# Controller.net
KiCad netlist of a schematic drawn in EAGLE
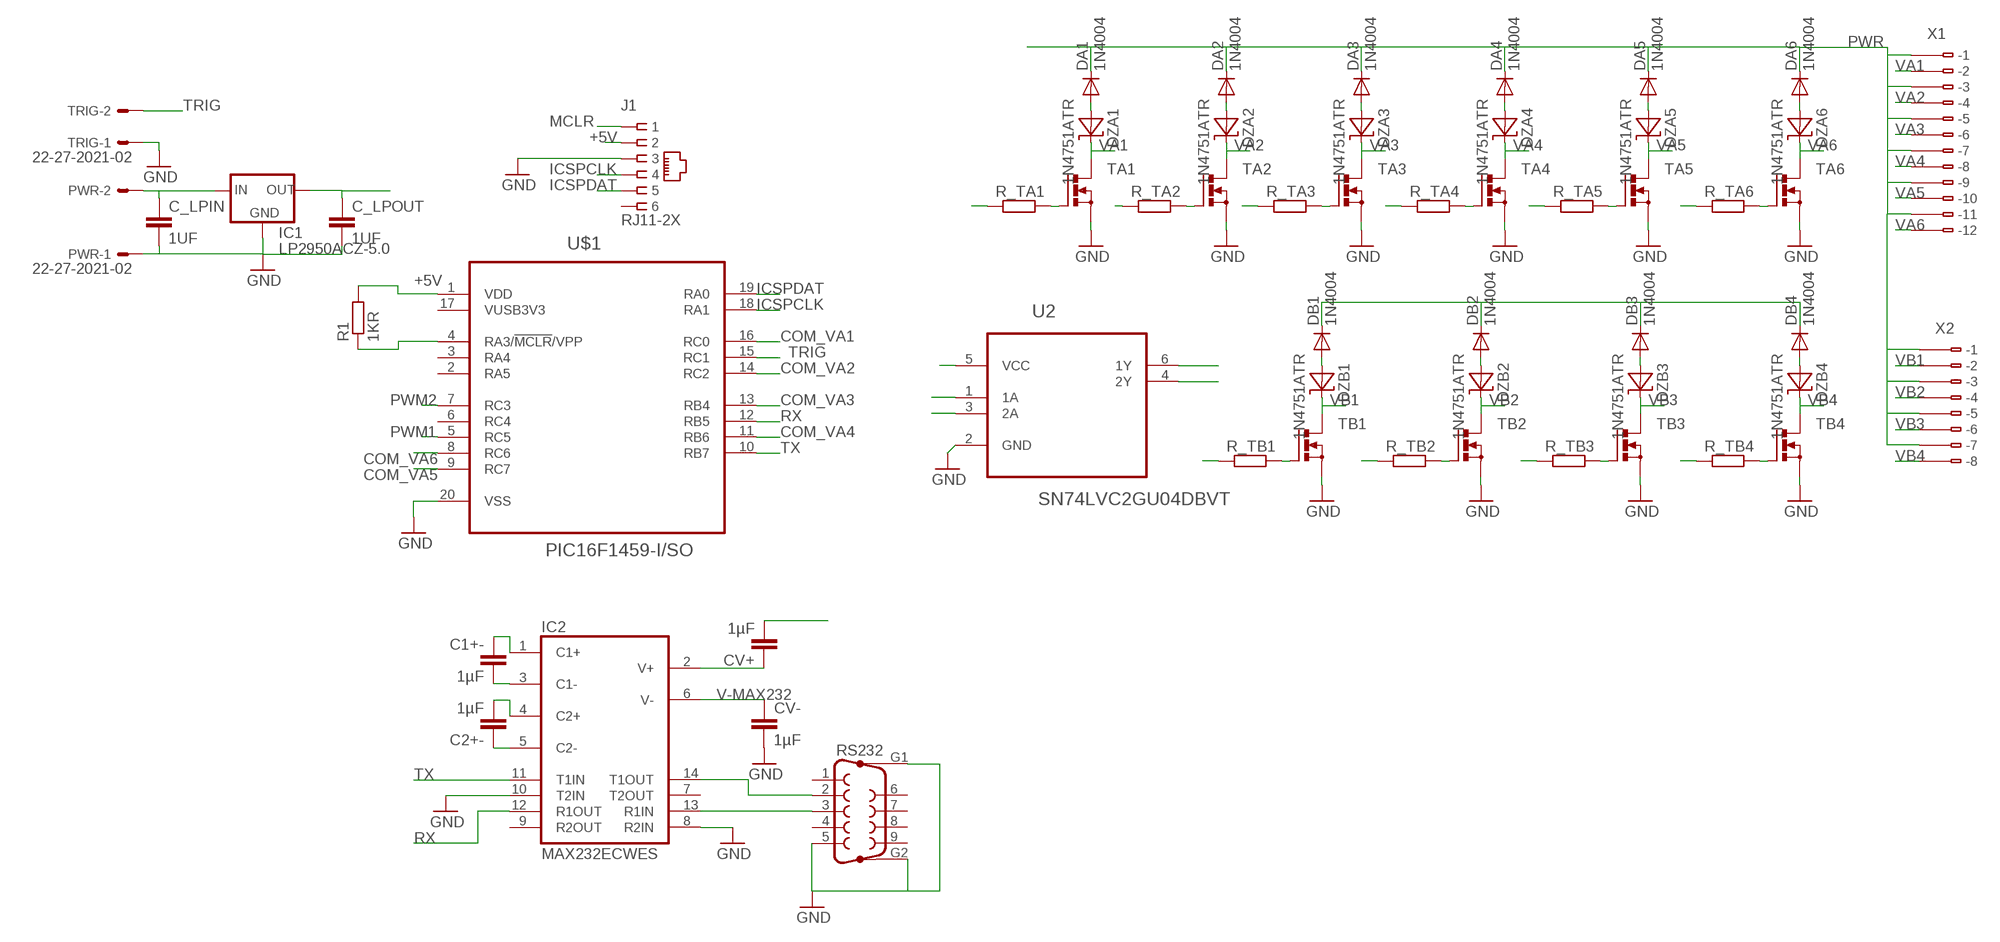
[diagram p0: schematic, sheet 1]

(export (version "E")
  (design (tool "Eeschema 10.0.6"))
  (components
    (comp (ref "C1+-")
      (value "1µF")
      (footprint "eagle-import:C0805")
      (libsource (lib "eagle-import") (part "C-EUC0805"))
    )
    (comp (ref "C2+-")
      (value "1µF")
      (footprint "eagle-import:C0805")
      (libsource (lib "eagle-import") (part "C-EUC0805"))
    )
    (comp (ref "CV+")
      (value "1µF")
      (footprint "eagle-import:C0805")
      (libsource (lib "eagle-import") (part "C-EUC0805"))
    )
    (comp (ref "CV-")
      (value "1µF")
      (footprint "eagle-import:C0805")
      (libsource (lib "eagle-import") (part "C-EUC0805"))
    )
    (comp (ref "C_LPIN")
      (value "1UF")
      (footprint "eagle-import:C0805")
      (libsource (lib "eagle-import") (part "C-EUC0805"))
    )
    (comp (ref "C_LPOUT")
      (value "1UF")
      (footprint "eagle-import:C0805")
      (libsource (lib "eagle-import") (part "C-EUC0805"))
    )
    (comp (ref "DA1")
      (value "1N4004")
      (footprint "eagle-import:DO41-10")
      (libsource (lib "eagle-import") (part "1N4004"))
    )
    (comp (ref "DA2")
      (value "1N4004")
      (footprint "eagle-import:DO41-10")
      (libsource (lib "eagle-import") (part "1N4004"))
    )
    (comp (ref "DA3")
      (value "1N4004")
      (footprint "eagle-import:DO41-10")
      (libsource (lib "eagle-import") (part "1N4004"))
    )
    (comp (ref "DA4")
      (value "1N4004")
      (footprint "eagle-import:DO41-10")
      (libsource (lib "eagle-import") (part "1N4004"))
    )
    (comp (ref "DA5")
      (value "1N4004")
      (footprint "eagle-import:DO41-10")
      (libsource (lib "eagle-import") (part "1N4004"))
    )
    (comp (ref "DA6")
      (value "1N4004")
      (footprint "eagle-import:DO41-10")
      (libsource (lib "eagle-import") (part "1N4004"))
    )
    (comp (ref "DB1")
      (value "1N4004")
      (footprint "eagle-import:DO41-10")
      (libsource (lib "eagle-import") (part "1N4004"))
    )
    (comp (ref "DB2")
      (value "1N4004")
      (footprint "eagle-import:DO41-10")
      (libsource (lib "eagle-import") (part "1N4004"))
    )
    (comp (ref "DB3")
      (value "1N4004")
      (footprint "eagle-import:DO41-10")
      (libsource (lib "eagle-import") (part "1N4004"))
    )
    (comp (ref "DB4")
      (value "1N4004")
      (footprint "eagle-import:DO41-10")
      (libsource (lib "eagle-import") (part "1N4004"))
    )
    (comp (ref "DZA1")
      (value "1N4751ATR")
      (footprint "eagle-import:DO41-7")
      (libsource (lib "eagle-import") (part "1N4751ATR"))
    )
    (comp (ref "DZA2")
      (value "1N4751ATR")
      (footprint "eagle-import:DO41-7")
      (libsource (lib "eagle-import") (part "1N4751ATR"))
    )
    (comp (ref "DZA3")
      (value "1N4751ATR")
      (footprint "eagle-import:DO41-7")
      (libsource (lib "eagle-import") (part "1N4751ATR"))
    )
    (comp (ref "DZA4")
      (value "1N4751ATR")
      (footprint "eagle-import:DO41-7")
      (libsource (lib "eagle-import") (part "1N4751ATR"))
    )
    (comp (ref "DZA5")
      (value "1N4751ATR")
      (footprint "eagle-import:DO41-7")
      (libsource (lib "eagle-import") (part "1N4751ATR"))
    )
    (comp (ref "DZA6")
      (value "1N4751ATR")
      (footprint "eagle-import:DO41-7")
      (libsource (lib "eagle-import") (part "1N4751ATR"))
    )
    (comp (ref "DZB1")
      (value "1N4751ATR")
      (footprint "eagle-import:DO41-7")
      (libsource (lib "eagle-import") (part "1N4751ATR"))
    )
    (comp (ref "DZB2")
      (value "1N4751ATR")
      (footprint "eagle-import:DO41-7")
      (libsource (lib "eagle-import") (part "1N4751ATR"))
    )
    (comp (ref "DZB3")
      (value "1N4751ATR")
      (footprint "eagle-import:DO41-7")
      (libsource (lib "eagle-import") (part "1N4751ATR"))
    )
    (comp (ref "DZB4")
      (value "1N4751ATR")
      (footprint "eagle-import:DO41-7")
      (libsource (lib "eagle-import") (part "1N4751ATR"))
    )
    (comp (ref "IC1")
      (value "LP2950ACZ-5.0")
      (footprint "eagle-import:TO92")
      (libsource (lib "eagle-import") (part "LP2950?ACZ-5.0"))
    )
    (comp (ref "IC2")
      (value "MAX232ECWES")
      (footprint "eagle-import:SO16")
      (libsource (lib "eagle-import") (part "MAX232ECWES"))
    )
    (comp (ref "J1")
      (value "RJ11-2X")
      (footprint "eagle-import:RJ11-NO_SHIELD")
      (fields (field (name "OC_FARNELL") "3363132"))
      (libsource (lib "eagle-import") (part "RJ11-2X"))
    )
    (comp (ref "PWR")
      (value "22-27-2021-02")
      (footprint "eagle-import:6410-02")
      (fields (field (name "OC_FARNELL") "9731148+1654528+1462641"))
      (libsource (lib "eagle-import") (part "22-?-0227-2021"))
    )
    (comp (ref "R1")
      (value "1KR")
      (footprint "eagle-import:R0805")
      (libsource (lib "eagle-import") (part "R-EU_R0805"))
    )
    (comp (ref "RS232")
      (value "F09HP")
      (footprint "eagle-import:F09HP")
      (fields (field (name "OC_FARNELL") "1084701"))
      (libsource (lib "eagle-import") (part "F09HP"))
    )
    (comp (ref "R_TA1")
      (value "R-EU_R0805")
      (footprint "eagle-import:R0805")
      (libsource (lib "eagle-import") (part "R-EU_R0805"))
    )
    (comp (ref "R_TA2")
      (value "R-EU_R0805")
      (footprint "eagle-import:R0805")
      (libsource (lib "eagle-import") (part "R-EU_R0805"))
    )
    (comp (ref "R_TA3")
      (value "R-EU_R0805")
      (footprint "eagle-import:R0805")
      (libsource (lib "eagle-import") (part "R-EU_R0805"))
    )
    (comp (ref "R_TA4")
      (value "R-EU_R0805")
      (footprint "eagle-import:R0805")
      (libsource (lib "eagle-import") (part "R-EU_R0805"))
    )
    (comp (ref "R_TA5")
      (value "R-EU_R0805")
      (footprint "eagle-import:R0805")
      (libsource (lib "eagle-import") (part "R-EU_R0805"))
    )
    (comp (ref "R_TA6")
      (value "R-EU_R0805")
      (footprint "eagle-import:R0805")
      (libsource (lib "eagle-import") (part "R-EU_R0805"))
    )
    (comp (ref "R_TB1")
      (value "R-EU_R0805")
      (footprint "eagle-import:R0805")
      (libsource (lib "eagle-import") (part "R-EU_R0805"))
    )
    (comp (ref "R_TB2")
      (value "R-EU_R0805")
      (footprint "eagle-import:R0805")
      (libsource (lib "eagle-import") (part "R-EU_R0805"))
    )
    (comp (ref "R_TB3")
      (value "R-EU_R0805")
      (footprint "eagle-import:R0805")
      (libsource (lib "eagle-import") (part "R-EU_R0805"))
    )
    (comp (ref "R_TB4")
      (value "R-EU_R0805")
      (footprint "eagle-import:R0805")
      (libsource (lib "eagle-import") (part "R-EU_R0805"))
    )
    (comp (ref "TA1")
      (value "BSS316N")
      (footprint "eagle-import:INF-PG-SOT23_N_1PRIMARY")
      (libsource (lib "eagle-import") (part "BSS316N"))
    )
    (comp (ref "TA2")
      (value "BSS316N")
      (footprint "eagle-import:INF-PG-SOT23_N_1PRIMARY")
      (libsource (lib "eagle-import") (part "BSS316N"))
    )
    (comp (ref "TA3")
      (value "BSS316N")
      (footprint "eagle-import:INF-PG-SOT23_N_1PRIMARY")
      (libsource (lib "eagle-import") (part "BSS316N"))
    )
    (comp (ref "TA4")
      (value "BSS316N")
      (footprint "eagle-import:INF-PG-SOT23_N_1PRIMARY")
      (libsource (lib "eagle-import") (part "BSS316N"))
    )
    (comp (ref "TA5")
      (value "BSS316N")
      (footprint "eagle-import:INF-PG-SOT23_N_1PRIMARY")
      (libsource (lib "eagle-import") (part "BSS316N"))
    )
    (comp (ref "TA6")
      (value "BSS316N")
      (footprint "eagle-import:INF-PG-SOT23_N_1PRIMARY")
      (libsource (lib "eagle-import") (part "BSS316N"))
    )
    (comp (ref "TB1")
      (value "BSS316N")
      (footprint "eagle-import:INF-PG-SOT23_N_1PRIMARY")
      (libsource (lib "eagle-import") (part "BSS316N"))
    )
    (comp (ref "TB2")
      (value "BSS316N")
      (footprint "eagle-import:INF-PG-SOT23_N_1PRIMARY")
      (libsource (lib "eagle-import") (part "BSS316N"))
    )
    (comp (ref "TB3")
      (value "BSS316N")
      (footprint "eagle-import:INF-PG-SOT23_N_1PRIMARY")
      (libsource (lib "eagle-import") (part "BSS316N"))
    )
    (comp (ref "TB4")
      (value "BSS316N")
      (footprint "eagle-import:INF-PG-SOT23_N_1PRIMARY")
      (libsource (lib "eagle-import") (part "BSS316N"))
    )
    (comp (ref "TRIG")
      (value "22-27-2021-02")
      (footprint "eagle-import:6410-02")
      (fields (field (name "OC_FARNELL") "9731148+1654528+1462641"))
      (libsource (lib "eagle-import") (part "22-?-0227-2021"))
    )
    (comp (ref "U$1")
      (value "PIC16F1459-I/SO")
      (footprint "eagle-import:SOIC127P1030X265-20N")
      (libsource (lib "eagle-import") (part "PIC16F1459-I/SO"))
    )
    (comp (ref "U2")
      (value "SN74LVC2GU04DBVT")
      (footprint "eagle-import:SOT95P280X145-6N")
      (libsource (lib "eagle-import") (part "SN74LVC2GU04DBVT"))
    )
    (comp (ref "X1")
      (value "233-212")
      (footprint "eagle-import:233-212")
      (libsource (lib "eagle-import") (part "233-212"))
    )
    (comp (ref "X2")
      (value "233-208")
      (footprint "eagle-import:233-208")
      (libsource (lib "eagle-import") (part "233-208"))
    )
  )
  (nets
    (net (code "1") (name "/+5V") (class "Default")
      (node (ref "CV+") (pin "2") (pinfunction "2_2") (pintype "passive"))
      (node (ref "C_LPOUT") (pin "1") (pinfunction "1_1") (pintype "passive"))
      (node (ref "IC1") (pin "1") (pinfunction "OUT_1") (pintype "passive"))
      (node (ref "J1") (pin "2") (pinfunction "2_2") (pintype "passive"))
      (node (ref "R1") (pin "2") (pinfunction "2_2") (pintype "passive"))
      (node (ref "U$1") (pin "1") (pinfunction "VDD_1") (pintype "power_in"))
      (node (ref "U2") (pin "5") (pinfunction "VCC_5") (pintype "power_in"))
    )
    (net (code "2") (name "/COM_VA1") (class "Default")
      (node (ref "R_TA1") (pin "1") (pinfunction "1_1") (pintype "passive"))
      (node (ref "U$1") (pin "16") (pinfunction "RC0_16") (pintype "bidirectional"))
    )
    (net (code "3") (name "/COM_VA2") (class "Default")
      (node (ref "R_TA2") (pin "1") (pinfunction "1_1") (pintype "passive"))
      (node (ref "U$1") (pin "14") (pinfunction "RC2_14") (pintype "bidirectional"))
    )
    (net (code "4") (name "/COM_VA3") (class "Default")
      (node (ref "R_TA3") (pin "1") (pinfunction "1_1") (pintype "passive"))
      (node (ref "U$1") (pin "13") (pinfunction "RB4_13") (pintype "bidirectional"))
    )
    (net (code "5") (name "/COM_VA4") (class "Default")
      (node (ref "R_TA4") (pin "1") (pinfunction "1_1") (pintype "passive"))
      (node (ref "U$1") (pin "11") (pinfunction "RB6_11") (pintype "bidirectional"))
    )
    (net (code "6") (name "/COM_VA5") (class "Default")
      (node (ref "R_TA5") (pin "1") (pinfunction "1_1") (pintype "passive"))
      (node (ref "U$1") (pin "9") (pinfunction "RC7_9") (pintype "bidirectional"))
    )
    (net (code "7") (name "/COM_VA6") (class "Default")
      (node (ref "R_TA6") (pin "1") (pinfunction "1_1") (pintype "passive"))
      (node (ref "U$1") (pin "8") (pinfunction "RC6_8") (pintype "bidirectional"))
    )
    (net (code "8") (name "/ICSPCLK") (class "Default")
      (node (ref "J1") (pin "4") (pinfunction "4_4") (pintype "passive"))
      (node (ref "U$1") (pin "18") (pinfunction "RA1_18") (pintype "bidirectional"))
    )
    (net (code "9") (name "/ICSPDAT") (class "Default")
      (node (ref "J1") (pin "5") (pinfunction "5_5") (pintype "passive"))
      (node (ref "U$1") (pin "19") (pinfunction "RA0_19") (pintype "bidirectional"))
    )
    (net (code "10") (name "/MCLR") (class "Default")
      (node (ref "J1") (pin "1") (pinfunction "1_1") (pintype "passive"))
      (node (ref "R1") (pin "1") (pinfunction "1_1") (pintype "passive"))
      (node (ref "U$1") (pin "4") (pinfunction "RA3/~{MCLR}/VPP_4") (pintype "bidirectional"))
    )
    (net (code "11") (name "/PWM1") (class "Default")
      (node (ref "R_TB1") (pin "1") (pinfunction "1_1") (pintype "passive"))
      (node (ref "U$1") (pin "5") (pinfunction "RC5_5") (pintype "bidirectional"))
      (node (ref "U2") (pin "1") (pinfunction "1A_1") (pintype "input"))
    )
    (net (code "12") (name "/PWM1_INV") (class "Default")
      (node (ref "R_TB3") (pin "1") (pinfunction "1_1") (pintype "passive"))
      (node (ref "U2") (pin "6") (pinfunction "1Y_6") (pintype "output"))
    )
    (net (code "13") (name "/PWM2") (class "Default")
      (node (ref "R_TB2") (pin "1") (pinfunction "1_1") (pintype "passive"))
      (node (ref "U$1") (pin "7") (pinfunction "RC3_7") (pintype "bidirectional"))
      (node (ref "U2") (pin "3") (pinfunction "2A_3") (pintype "input"))
    )
    (net (code "14") (name "/PWM2_INV") (class "Default")
      (node (ref "R_TB4") (pin "1") (pinfunction "1_1") (pintype "passive"))
      (node (ref "U2") (pin "4") (pinfunction "2Y_4") (pintype "output"))
    )
    (net (code "15") (name "/PWR") (class "Default")
      (node (ref "C_LPIN") (pin "1") (pinfunction "1_1") (pintype "passive"))
      (node (ref "DA1") (pin "C") (pinfunction "C_C") (pintype "passive"))
      (node (ref "DA2") (pin "C") (pinfunction "C_C") (pintype "passive"))
      (node (ref "DA3") (pin "C") (pinfunction "C_C") (pintype "passive"))
      (node (ref "DA4") (pin "C") (pinfunction "C_C") (pintype "passive"))
      (node (ref "DA5") (pin "C") (pinfunction "C_C") (pintype "passive"))
      (node (ref "DA6") (pin "C") (pinfunction "C_C") (pintype "passive"))
      (node (ref "IC1") (pin "3") (pinfunction "IN_3") (pintype "input"))
      (node (ref "PWR") (pin "2") (pinfunction "S_2") (pintype "passive"))
      (node (ref "X1") (pin "B1") (pinfunction "B-1_B1") (pintype "passive"))
      (node (ref "X1") (pin "B11") (pinfunction "B-11_B11") (pintype "passive"))
      (node (ref "X1") (pin "B3") (pinfunction "B-3_B3") (pintype "passive"))
      (node (ref "X1") (pin "B5") (pinfunction "B-5_B5") (pintype "passive"))
      (node (ref "X1") (pin "B7") (pinfunction "B-7_B7") (pintype "passive"))
      (node (ref "X1") (pin "B9") (pinfunction "B-9_B9") (pintype "passive"))
      (node (ref "X2") (pin "B1") (pinfunction "B-1_B1") (pintype "passive"))
      (node (ref "X2") (pin "B3") (pinfunction "B-3_B3") (pintype "passive"))
      (node (ref "X2") (pin "B5") (pinfunction "B-5_B5") (pintype "passive"))
      (node (ref "X2") (pin "B7") (pinfunction "B-7_B7") (pintype "passive"))
    )
    (net (code "16") (name "/RX") (class "Default")
      (node (ref "IC2") (pin "12") (pinfunction "R1OUT_12") (pintype "output"))
      (node (ref "U$1") (pin "12") (pinfunction "RB5_12") (pintype "bidirectional"))
    )
    (net (code "17") (name "/TRIG") (class "Default")
      (node (ref "TRIG") (pin "2") (pinfunction "S_2") (pintype "passive"))
      (node (ref "U$1") (pin "15") (pinfunction "RC1_15") (pintype "bidirectional"))
    )
    (net (code "18") (name "/TX") (class "Default")
      (node (ref "IC2") (pin "11") (pinfunction "T1IN_11") (pintype "input"))
      (node (ref "U$1") (pin "10") (pinfunction "RB7_10") (pintype "bidirectional"))
    )
    (net (code "19") (name "/V-MAX232") (class "Default")
      (node (ref "CV-") (pin "1") (pinfunction "1_1") (pintype "passive"))
      (node (ref "IC2") (pin "6") (pinfunction "V-_6") (pintype "bidirectional"))
    )
    (net (code "20") (name "/VA1") (class "Default")
      (node (ref "DZA1") (pin "C") (pinfunction "C_C") (pintype "passive"))
      (node (ref "TA1") (pin "3") (pinfunction "D_3") (pintype "passive"))
      (node (ref "X1") (pin "B2") (pinfunction "B-2_B2") (pintype "passive"))
    )
    (net (code "21") (name "/VA2") (class "Default")
      (node (ref "DZA2") (pin "C") (pinfunction "C_C") (pintype "passive"))
      (node (ref "TA2") (pin "3") (pinfunction "D_3") (pintype "passive"))
      (node (ref "X1") (pin "B4") (pinfunction "B-4_B4") (pintype "passive"))
    )
    (net (code "22") (name "/VA3") (class "Default")
      (node (ref "DZA3") (pin "C") (pinfunction "C_C") (pintype "passive"))
      (node (ref "TA3") (pin "3") (pinfunction "D_3") (pintype "passive"))
      (node (ref "X1") (pin "B6") (pinfunction "B-6_B6") (pintype "passive"))
    )
    (net (code "23") (name "/VA4") (class "Default")
      (node (ref "DZA4") (pin "C") (pinfunction "C_C") (pintype "passive"))
      (node (ref "TA4") (pin "3") (pinfunction "D_3") (pintype "passive"))
      (node (ref "X1") (pin "B8") (pinfunction "B-8_B8") (pintype "passive"))
    )
    (net (code "24") (name "/VA5") (class "Default")
      (node (ref "DZA5") (pin "C") (pinfunction "C_C") (pintype "passive"))
      (node (ref "TA5") (pin "3") (pinfunction "D_3") (pintype "passive"))
      (node (ref "X1") (pin "B10") (pinfunction "B-10_B10") (pintype "passive"))
    )
    (net (code "25") (name "/VA6") (class "Default")
      (node (ref "DZA6") (pin "C") (pinfunction "C_C") (pintype "passive"))
      (node (ref "TA6") (pin "3") (pinfunction "D_3") (pintype "passive"))
      (node (ref "X1") (pin "B12") (pinfunction "B-12_B12") (pintype "passive"))
    )
    (net (code "26") (name "/VB1") (class "Default")
      (node (ref "DZB1") (pin "C") (pinfunction "C_C") (pintype "passive"))
      (node (ref "TB1") (pin "3") (pinfunction "D_3") (pintype "passive"))
      (node (ref "X2") (pin "B2") (pinfunction "B-2_B2") (pintype "passive"))
    )
    (net (code "27") (name "/VB2") (class "Default")
      (node (ref "DZB2") (pin "C") (pinfunction "C_C") (pintype "passive"))
      (node (ref "TB2") (pin "3") (pinfunction "D_3") (pintype "passive"))
      (node (ref "X2") (pin "B4") (pinfunction "B-4_B4") (pintype "passive"))
    )
    (net (code "28") (name "/VB3") (class "Default")
      (node (ref "DZB3") (pin "C") (pinfunction "C_C") (pintype "passive"))
      (node (ref "TB3") (pin "3") (pinfunction "D_3") (pintype "passive"))
      (node (ref "X2") (pin "B6") (pinfunction "B-6_B6") (pintype "passive"))
    )
    (net (code "29") (name "/VB4") (class "Default")
      (node (ref "DZB4") (pin "C") (pinfunction "C_C") (pintype "passive"))
      (node (ref "TB4") (pin "3") (pinfunction "D_3") (pintype "passive"))
      (node (ref "X2") (pin "B8") (pinfunction "B-8_B8") (pintype "passive"))
    )
    (net (code "30") (name "/VUSB3V3") (class "Default")
      (node (ref "U$1") (pin "17") (pinfunction "VUSB3V3_17") (pintype "power_in"))
    )
    (net (code "31") (name "GND") (class "Default")
      (node (ref "CV-") (pin "2") (pinfunction "2_2") (pintype "passive"))
      (node (ref "C_LPIN") (pin "2") (pinfunction "2_2") (pintype "passive"))
      (node (ref "C_LPOUT") (pin "2") (pinfunction "2_2") (pintype "passive"))
      (node (ref "IC1") (pin "2") (pinfunction "GND_2") (pintype "input"))
      (node (ref "IC2") (pin "10") (pinfunction "T2IN_10") (pintype "input"))
      (node (ref "IC2") (pin "8") (pinfunction "R2IN_8") (pintype "input"))
      (node (ref "J1") (pin "3") (pinfunction "3_3") (pintype "passive"))
      (node (ref "PWR") (pin "1") (pinfunction "S_1") (pintype "passive"))
      (node (ref "RS232") (pin "5") (pinfunction "5_5") (pintype "passive"))
      (node (ref "RS232") (pin "G1") (pinfunction "G1_G1") (pintype "passive"))
      (node (ref "RS232") (pin "G2") (pinfunction "G2_G2") (pintype "passive"))
      (node (ref "TA1") (pin "2") (pinfunction "S_2") (pintype "passive"))
      (node (ref "TA2") (pin "2") (pinfunction "S_2") (pintype "passive"))
      (node (ref "TA3") (pin "2") (pinfunction "S_2") (pintype "passive"))
      (node (ref "TA4") (pin "2") (pinfunction "S_2") (pintype "passive"))
      (node (ref "TA5") (pin "2") (pinfunction "S_2") (pintype "passive"))
      (node (ref "TA6") (pin "2") (pinfunction "S_2") (pintype "passive"))
      (node (ref "TB1") (pin "2") (pinfunction "S_2") (pintype "passive"))
      (node (ref "TB2") (pin "2") (pinfunction "S_2") (pintype "passive"))
      (node (ref "TB3") (pin "2") (pinfunction "S_2") (pintype "passive"))
      (node (ref "TB4") (pin "2") (pinfunction "S_2") (pintype "passive"))
      (node (ref "TRIG") (pin "1") (pinfunction "S_1") (pintype "passive"))
      (node (ref "U$1") (pin "20") (pinfunction "VSS_20") (pintype "power_in"))
      (node (ref "U2") (pin "2") (pinfunction "GND_2") (pintype "passive"))
    )
    (net (code "32") (name "Net-(DA1-PadA)") (class "Default")
      (node (ref "DA1") (pin "A") (pinfunction "A_A") (pintype "passive"))
      (node (ref "DZA1") (pin "A") (pinfunction "A_A") (pintype "passive"))
    )
    (net (code "33") (name "Net-(DA2-PadA)") (class "Default")
      (node (ref "DA2") (pin "A") (pinfunction "A_A") (pintype "passive"))
      (node (ref "DZA2") (pin "A") (pinfunction "A_A") (pintype "passive"))
    )
    (net (code "34") (name "Net-(DA3-PadA)") (class "Default")
      (node (ref "DA3") (pin "A") (pinfunction "A_A") (pintype "passive"))
      (node (ref "DZA3") (pin "A") (pinfunction "A_A") (pintype "passive"))
    )
    (net (code "35") (name "Net-(DA4-PadA)") (class "Default")
      (node (ref "DA4") (pin "A") (pinfunction "A_A") (pintype "passive"))
      (node (ref "DZA4") (pin "A") (pinfunction "A_A") (pintype "passive"))
    )
    (net (code "36") (name "Net-(DA5-PadA)") (class "Default")
      (node (ref "DA5") (pin "A") (pinfunction "A_A") (pintype "passive"))
      (node (ref "DZA5") (pin "A") (pinfunction "A_A") (pintype "passive"))
    )
    (net (code "37") (name "Net-(DA6-PadA)") (class "Default")
      (node (ref "DA6") (pin "A") (pinfunction "A_A") (pintype "passive"))
      (node (ref "DZA6") (pin "A") (pinfunction "A_A") (pintype "passive"))
    )
    (net (code "38") (name "Net-(DB1-PadA)") (class "Default")
      (node (ref "DB1") (pin "A") (pinfunction "A_A") (pintype "passive"))
      (node (ref "DZB1") (pin "A") (pinfunction "A_A") (pintype "passive"))
    )
    (net (code "39") (name "Net-(DB1-PadC)") (class "Default")
      (node (ref "DB1") (pin "C") (pinfunction "C_C") (pintype "passive"))
      (node (ref "DB2") (pin "C") (pinfunction "C_C") (pintype "passive"))
      (node (ref "DB3") (pin "C") (pinfunction "C_C") (pintype "passive"))
      (node (ref "DB4") (pin "C") (pinfunction "C_C") (pintype "passive"))
    )
    (net (code "40") (name "Net-(DB2-PadA)") (class "Default")
      (node (ref "DB2") (pin "A") (pinfunction "A_A") (pintype "passive"))
      (node (ref "DZB2") (pin "A") (pinfunction "A_A") (pintype "passive"))
    )
    (net (code "41") (name "Net-(DB3-PadA)") (class "Default")
      (node (ref "DB3") (pin "A") (pinfunction "A_A") (pintype "passive"))
      (node (ref "DZB3") (pin "A") (pinfunction "A_A") (pintype "passive"))
    )
    (net (code "42") (name "Net-(DB4-PadA)") (class "Default")
      (node (ref "DB4") (pin "A") (pinfunction "A_A") (pintype "passive"))
      (node (ref "DZB4") (pin "A") (pinfunction "A_A") (pintype "passive"))
    )
    (net (code "43") (name "Net-(IC2A-C1+)") (class "Default")
      (node (ref "C1+-") (pin "1") (pinfunction "1_1") (pintype "passive"))
      (node (ref "IC2") (pin "1") (pinfunction "C1+_1") (pintype "bidirectional"))
    )
    (net (code "44") (name "Net-(IC2A-C1-)") (class "Default")
      (node (ref "C1+-") (pin "2") (pinfunction "2_2") (pintype "passive"))
      (node (ref "IC2") (pin "3") (pinfunction "C1-_3") (pintype "bidirectional"))
    )
    (net (code "45") (name "Net-(IC2A-C2+)") (class "Default")
      (node (ref "C2+-") (pin "2") (pinfunction "2_2") (pintype "passive"))
      (node (ref "IC2") (pin "4") (pinfunction "C2+_4") (pintype "bidirectional"))
    )
    (net (code "46") (name "Net-(IC2A-C2-)") (class "Default")
      (node (ref "C2+-") (pin "1") (pinfunction "1_1") (pintype "passive"))
      (node (ref "IC2") (pin "5") (pinfunction "C2-_5") (pintype "bidirectional"))
    )
    (net (code "47") (name "Net-(IC2A-R1IN)") (class "Default")
      (node (ref "IC2") (pin "13") (pinfunction "R1IN_13") (pintype "input"))
      (node (ref "RS232") (pin "3") (pinfunction "3_3") (pintype "passive"))
    )
    (net (code "48") (name "Net-(IC2A-T1OUT)") (class "Default")
      (node (ref "IC2") (pin "14") (pinfunction "T1OUT_14") (pintype "output"))
      (node (ref "RS232") (pin "2") (pinfunction "2_2") (pintype "passive"))
    )
    (net (code "49") (name "Net-(IC2A-V+)") (class "Default")
      (node (ref "CV+") (pin "1") (pinfunction "1_1") (pintype "passive"))
      (node (ref "IC2") (pin "2") (pinfunction "V+_2") (pintype "bidirectional"))
    )
    (net (code "50") (name "Net-(TA1-G)") (class "Default")
      (node (ref "R_TA1") (pin "2") (pinfunction "2_2") (pintype "passive"))
      (node (ref "TA1") (pin "1") (pinfunction "G_1") (pintype "passive"))
    )
    (net (code "51") (name "Net-(TA2-G)") (class "Default")
      (node (ref "R_TA2") (pin "2") (pinfunction "2_2") (pintype "passive"))
      (node (ref "TA2") (pin "1") (pinfunction "G_1") (pintype "passive"))
    )
    (net (code "52") (name "Net-(TA3-G)") (class "Default")
      (node (ref "R_TA3") (pin "2") (pinfunction "2_2") (pintype "passive"))
      (node (ref "TA3") (pin "1") (pinfunction "G_1") (pintype "passive"))
    )
    (net (code "53") (name "Net-(TA4-G)") (class "Default")
      (node (ref "R_TA4") (pin "2") (pinfunction "2_2") (pintype "passive"))
      (node (ref "TA4") (pin "1") (pinfunction "G_1") (pintype "passive"))
    )
    (net (code "54") (name "Net-(TA5-G)") (class "Default")
      (node (ref "R_TA5") (pin "2") (pinfunction "2_2") (pintype "passive"))
      (node (ref "TA5") (pin "1") (pinfunction "G_1") (pintype "passive"))
    )
    (net (code "55") (name "Net-(TA6-G)") (class "Default")
      (node (ref "R_TA6") (pin "2") (pinfunction "2_2") (pintype "passive"))
      (node (ref "TA6") (pin "1") (pinfunction "G_1") (pintype "passive"))
    )
    (net (code "56") (name "Net-(TB1-G)") (class "Default")
      (node (ref "R_TB1") (pin "2") (pinfunction "2_2") (pintype "passive"))
      (node (ref "TB1") (pin "1") (pinfunction "G_1") (pintype "passive"))
    )
    (net (code "57") (name "Net-(TB2-G)") (class "Default")
      (node (ref "R_TB2") (pin "2") (pinfunction "2_2") (pintype "passive"))
      (node (ref "TB2") (pin "1") (pinfunction "G_1") (pintype "passive"))
    )
    (net (code "58") (name "Net-(TB3-G)") (class "Default")
      (node (ref "R_TB3") (pin "2") (pinfunction "2_2") (pintype "passive"))
      (node (ref "TB3") (pin "1") (pinfunction "G_1") (pintype "passive"))
    )
    (net (code "59") (name "Net-(TB4-G)") (class "Default")
      (node (ref "R_TB4") (pin "2") (pinfunction "2_2") (pintype "passive"))
      (node (ref "TB4") (pin "1") (pinfunction "G_1") (pintype "passive"))
    )
    (net (code "60") (name "unconnected-(IC2A-R2OUT-Pad9)") (class "Default")
      (node (ref "IC2") (pin "9") (pinfunction "R2OUT_9") (pintype "output"))
    )
    (net (code "61") (name "unconnected-(IC2A-T2OUT-Pad7)") (class "Default")
      (node (ref "IC2") (pin "7") (pinfunction "T2OUT_7") (pintype "output"))
    )
    (net (code "62") (name "unconnected-(J1-Pad6)") (class "Default")
      (node (ref "J1") (pin "6") (pinfunction "6_6") (pintype "passive"))
    )
    (net (code "63") (name "unconnected-(RS232-Pad1)") (class "Default")
      (node (ref "RS232") (pin "1") (pinfunction "1_1") (pintype "passive"))
    )
    (net (code "64") (name "unconnected-(RS232-Pad4)") (class "Default")
      (node (ref "RS232") (pin "4") (pinfunction "4_4") (pintype "passive"))
    )
    (net (code "65") (name "unconnected-(RS232-Pad6)") (class "Default")
      (node (ref "RS232") (pin "6") (pinfunction "6_6") (pintype "passive"))
    )
    (net (code "66") (name "unconnected-(RS232-Pad7)") (class "Default")
      (node (ref "RS232") (pin "7") (pinfunction "7_7") (pintype "passive"))
    )
    (net (code "67") (name "unconnected-(RS232-Pad8)") (class "Default")
      (node (ref "RS232") (pin "8") (pinfunction "8_8") (pintype "passive"))
    )
    (net (code "68") (name "unconnected-(RS232-Pad9)") (class "Default")
      (node (ref "RS232") (pin "9") (pinfunction "9_9") (pintype "passive"))
    )
    (net (code "69") (name "unconnected-(U$1-RA4-Pad3)") (class "Default")
      (node (ref "U$1") (pin "3") (pinfunction "RA4_3") (pintype "bidirectional"))
    )
    (net (code "70") (name "unconnected-(U$1-RA5-Pad2)") (class "Default")
      (node (ref "U$1") (pin "2") (pinfunction "RA5_2") (pintype "bidirectional"))
    )
    (net (code "71") (name "unconnected-(U$1-RC4-Pad6)") (class "Default")
      (node (ref "U$1") (pin "6") (pinfunction "RC4_6") (pintype "bidirectional"))
    )
    (net (code "72") (name "unconnected-(X1--1-PadA1)") (class "Default")
      (node (ref "X1") (pin "A1") (pinfunction "-1_A1") (pintype "passive"))
    )
    (net (code "73") (name "unconnected-(X1--2-PadA2)") (class "Default")
      (node (ref "X1") (pin "A2") (pinfunction "-2_A2") (pintype "passive"))
    )
    (net (code "74") (name "unconnected-(X1--3-PadA3)") (class "Default")
      (node (ref "X1") (pin "A3") (pinfunction "-3_A3") (pintype "passive"))
    )
    (net (code "75") (name "unconnected-(X1--4-PadA4)") (class "Default")
      (node (ref "X1") (pin "A4") (pinfunction "-4_A4") (pintype "passive"))
    )
    (net (code "76") (name "unconnected-(X1--5-PadA5)") (class "Default")
      (node (ref "X1") (pin "A5") (pinfunction "-5_A5") (pintype "passive"))
    )
    (net (code "77") (name "unconnected-(X1--6-PadA6)") (class "Default")
      (node (ref "X1") (pin "A6") (pinfunction "-6_A6") (pintype "passive"))
    )
    (net (code "78") (name "unconnected-(X1--7-PadA7)") (class "Default")
      (node (ref "X1") (pin "A7") (pinfunction "-7_A7") (pintype "passive"))
    )
    (net (code "79") (name "unconnected-(X1--8-PadA8)") (class "Default")
      (node (ref "X1") (pin "A8") (pinfunction "-8_A8") (pintype "passive"))
    )
    (net (code "80") (name "unconnected-(X1--9-PadA9)") (class "Default")
      (node (ref "X1") (pin "A9") (pinfunction "-9_A9") (pintype "passive"))
    )
    (net (code "81") (name "unconnected-(X1--10-PadA10)") (class "Default")
      (node (ref "X1") (pin "A10") (pinfunction "-10_A10") (pintype "passive"))
    )
    (net (code "82") (name "unconnected-(X1--11-PadA11)") (class "Default")
      (node (ref "X1") (pin "A11") (pinfunction "-11_A11") (pintype "passive"))
    )
    (net (code "83") (name "unconnected-(X1--12-PadA12)") (class "Default")
      (node (ref "X1") (pin "A12") (pinfunction "-12_A12") (pintype "passive"))
    )
    (net (code "84") (name "unconnected-(X2--1-PadA1)") (class "Default")
      (node (ref "X2") (pin "A1") (pinfunction "-1_A1") (pintype "passive"))
    )
    (net (code "85") (name "unconnected-(X2--2-PadA2)") (class "Default")
      (node (ref "X2") (pin "A2") (pinfunction "-2_A2") (pintype "passive"))
    )
    (net (code "86") (name "unconnected-(X2--3-PadA3)") (class "Default")
      (node (ref "X2") (pin "A3") (pinfunction "-3_A3") (pintype "passive"))
    )
    (net (code "87") (name "unconnected-(X2--4-PadA4)") (class "Default")
      (node (ref "X2") (pin "A4") (pinfunction "-4_A4") (pintype "passive"))
    )
    (net (code "88") (name "unconnected-(X2--5-PadA5)") (class "Default")
      (node (ref "X2") (pin "A5") (pinfunction "-5_A5") (pintype "passive"))
    )
    (net (code "89") (name "unconnected-(X2--6-PadA6)") (class "Default")
      (node (ref "X2") (pin "A6") (pinfunction "-6_A6") (pintype "passive"))
    )
    (net (code "90") (name "unconnected-(X2--7-PadA7)") (class "Default")
      (node (ref "X2") (pin "A7") (pinfunction "-7_A7") (pintype "passive"))
    )
    (net (code "91") (name "unconnected-(X2--8-PadA8)") (class "Default")
      (node (ref "X2") (pin "A8") (pinfunction "-8_A8") (pintype "passive"))
    )
  )
)
